# CATS-EUROC-RF.net
KiCad netlist of a schematic drawn in Altium Designer
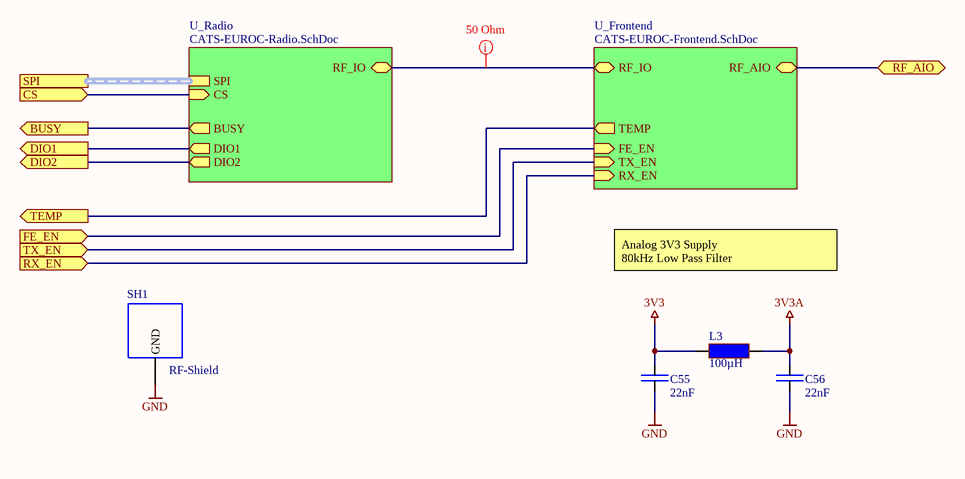
[diagram p0: CATS-EUROC-RF.SchDoc]

(export (version "E")
  (design (tool "Eeschema 10.0.6"))
  (components
    (comp (ref "C55")
      (value "22nF")
      (footprint "SMD Keramikkondensator 0805")
      (description "SMD Ceramic Capacitor E6")
      (libsource (lib "CATS-EUROC") (part "E6 - 22nF"))
    )
    (comp (ref "C56")
      (value "22nF")
      (footprint "SMD Keramikkondensator 0805")
      (description "SMD Ceramic Capacitor E6")
      (libsource (lib "CATS-EUROC") (part "E6 - 22nF"))
    )
    (comp (ref "L3")
      (value "100µH")
      (footprint "SMD Inductor 1812")
      (description "0.25A 100µH ±20% 144mΩ SMD Power Inductors")
      (libsource (lib "Inductors") (part "Inductor 100µH / 0.25A"))
    )
    (comp (ref "SH1")
      (value "RF-Shield")
      (footprint "SMD Shield MS183-10")
      (description "RF Shield Shield, 1-Piece 0.413\" (10.50mm) X 0.720\" (18.30mm) Non-Vented Solder")
      (libsource (lib "RF") (part "RF-Shield 18x10mm"))
    )
  )
  (nets
    (net (code "13") (name "3V3") (class "Default")
      (node (ref "C55") (pin "2") (pinfunction "2_2") (pintype "passive"))
      (node (ref "L3") (pin "1") (pinfunction "1_1") (pintype "passive"))
    )
    (net (code "14") (name "3V3A") (class "Default")
      (node (ref "C56") (pin "2") (pinfunction "2_2") (pintype "passive"))
      (node (ref "L3") (pin "2") (pinfunction "2_2") (pintype "passive"))
    )
    (net (code "15") (name "GND") (class "Default")
      (node (ref "C55") (pin "1") (pinfunction "1_1") (pintype "passive"))
      (node (ref "C56") (pin "1") (pinfunction "1_1") (pintype "passive"))
      (node (ref "SH1") (pin "1") (pinfunction "GND_1") (pintype "passive"))
    )
  )
)
